# host_board.net
KiCad netlist of a schematic drawn in Altium Designer
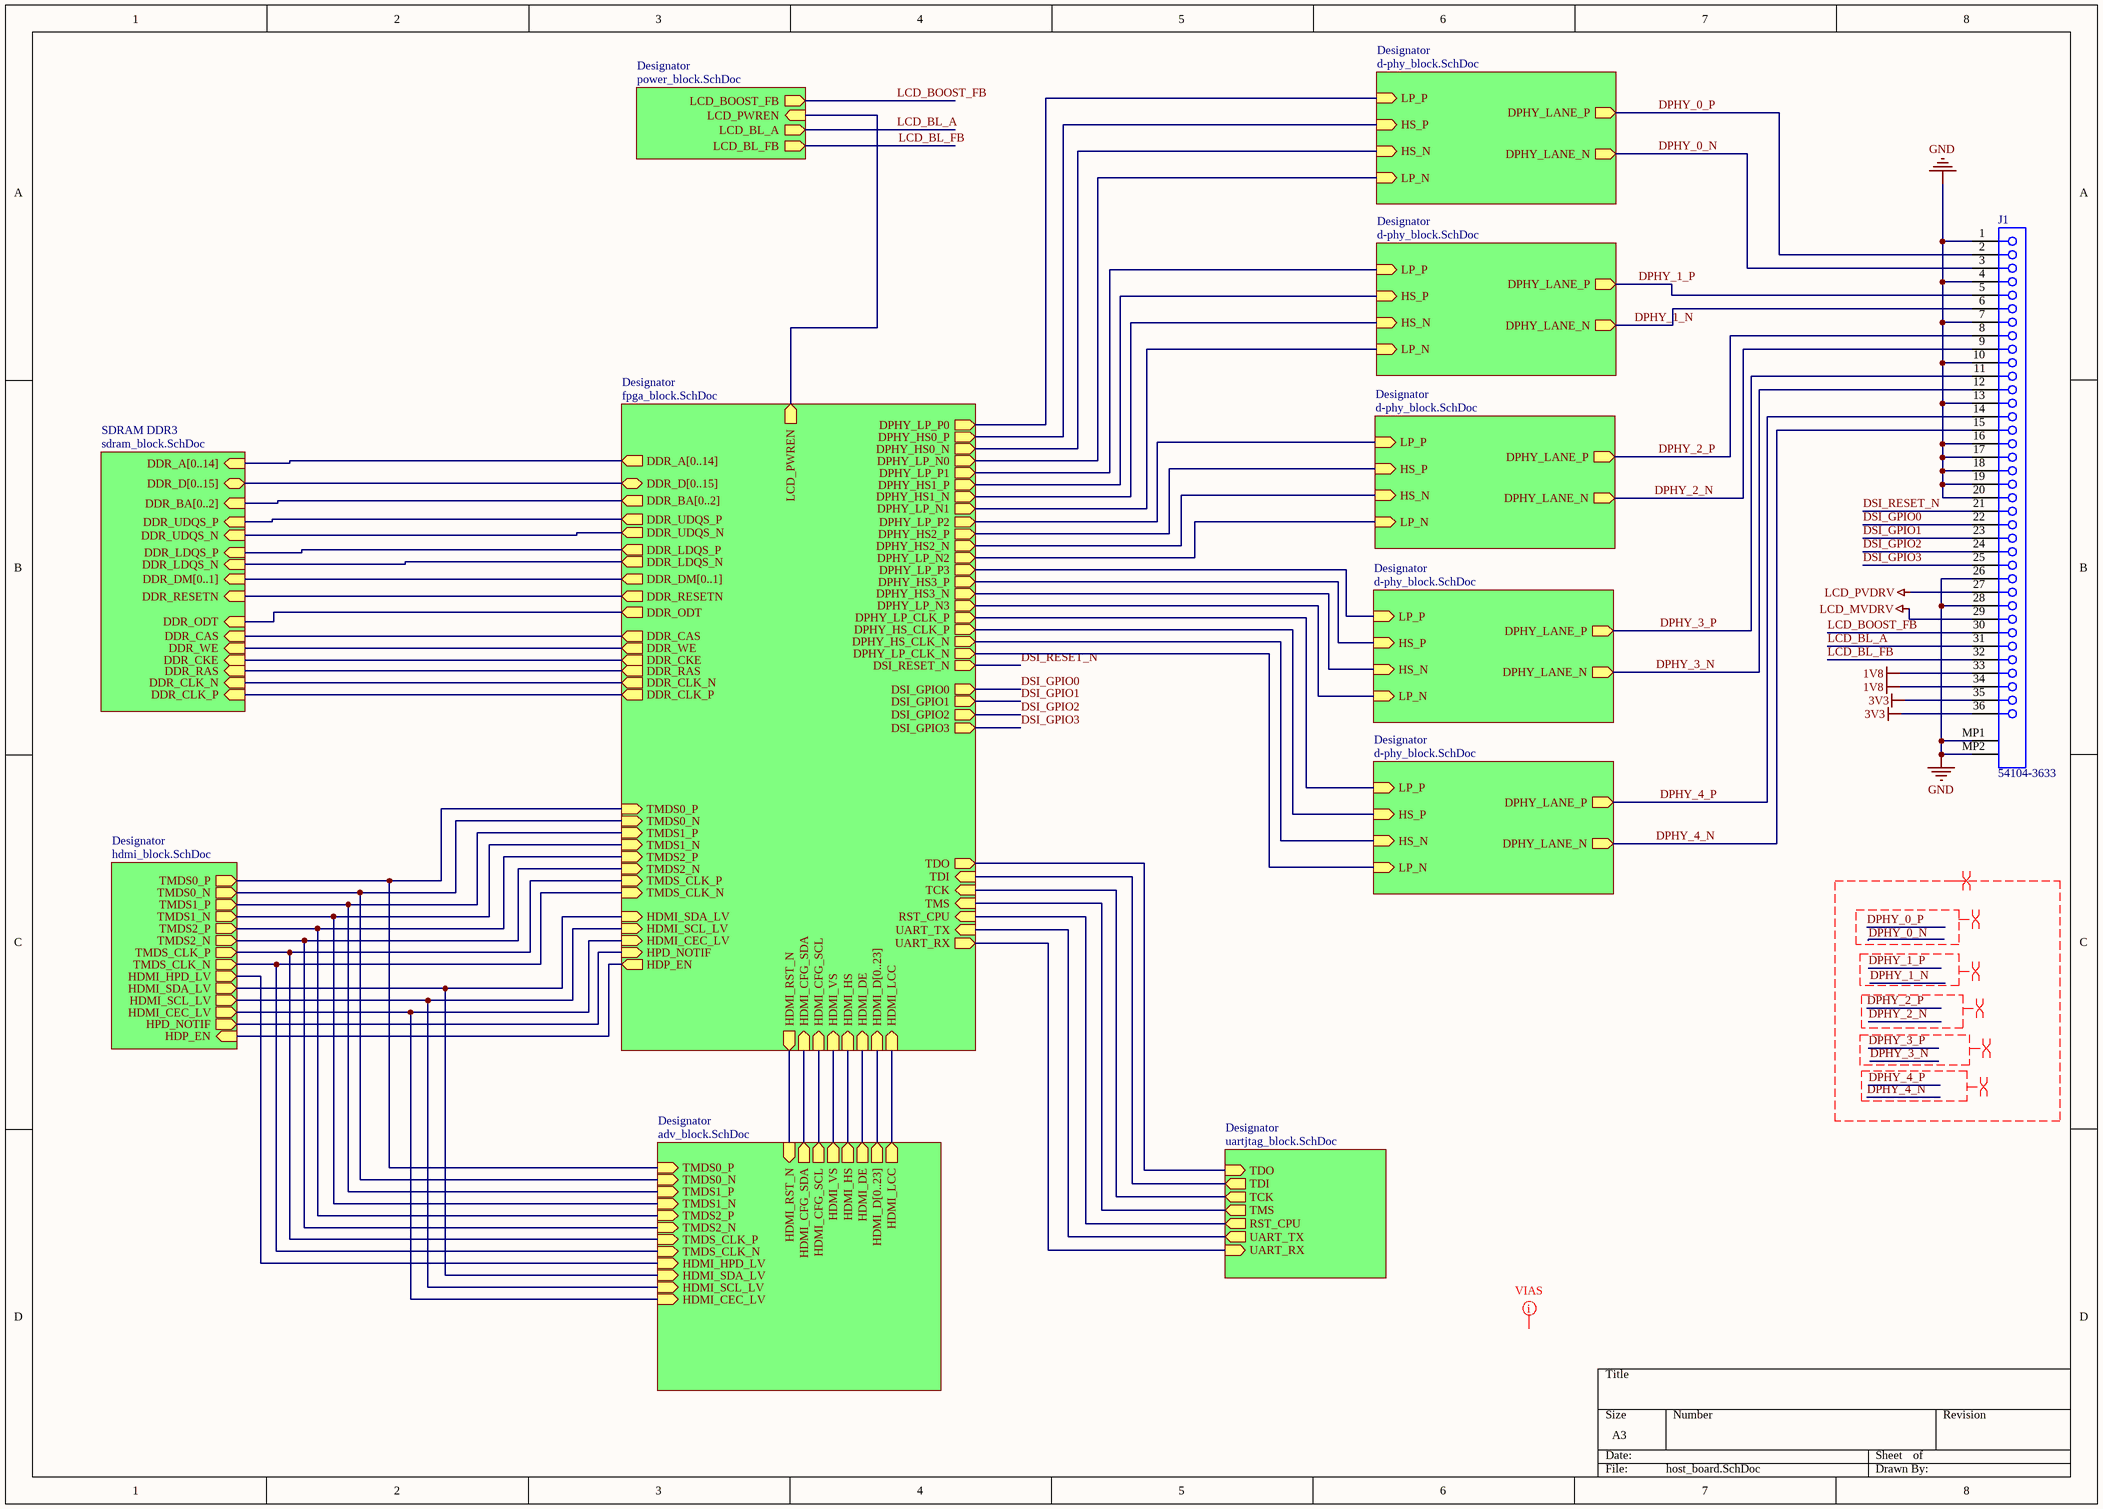
[diagram p0: host_board.SchDoc]

(export (version "E")
  (design (tool "Eeschema 10.0.6"))
  (components
    (comp (ref "J1")
      (value "54104-3633")
      (footprint "MOLX-54104-3633")
      (fields (field (name "MANUFACTURER") "Molex"))
      (libsource (lib "Molex FFC - FPC Connectors (SMT)") (part "54104-3633"))
    )
  )
  (nets
    (net (code "17") (name "/DPHY_0_N") (class "Default")
      (node (ref "J1") (pin "3") (pinfunction "3_3") (pintype "passive"))
    )
    (net (code "18") (name "/DPHY_0_P") (class "Default")
      (node (ref "J1") (pin "2") (pinfunction "2_2") (pintype "passive"))
    )
    (net (code "19") (name "/DPHY_1_N") (class "Default")
      (node (ref "J1") (pin "6") (pinfunction "6_6") (pintype "passive"))
    )
    (net (code "20") (name "/DPHY_1_P") (class "Default")
      (node (ref "J1") (pin "5") (pinfunction "5_5") (pintype "passive"))
    )
    (net (code "21") (name "/DPHY_2_N") (class "Default")
      (node (ref "J1") (pin "9") (pinfunction "9_9") (pintype "passive"))
    )
    (net (code "22") (name "/DPHY_2_P") (class "Default")
      (node (ref "J1") (pin "8") (pinfunction "8_8") (pintype "passive"))
    )
    (net (code "23") (name "/DPHY_3_N") (class "Default")
      (node (ref "J1") (pin "12") (pinfunction "12_12") (pintype "passive"))
    )
    (net (code "24") (name "/DPHY_3_P") (class "Default")
      (node (ref "J1") (pin "11") (pinfunction "11_11") (pintype "passive"))
    )
    (net (code "25") (name "/DPHY_4_N") (class "Default")
      (node (ref "J1") (pin "15") (pinfunction "15_15") (pintype "passive"))
    )
    (net (code "26") (name "/DPHY_4_P") (class "Default")
      (node (ref "J1") (pin "14") (pinfunction "14_14") (pintype "passive"))
    )
    (net (code "53") (name "/DSI_GPIO0") (class "Default")
      (node (ref "J1") (pin "22") (pinfunction "22_22") (pintype "passive"))
    )
    (net (code "54") (name "/DSI_GPIO1") (class "Default")
      (node (ref "J1") (pin "23") (pinfunction "23_23") (pintype "passive"))
    )
    (net (code "55") (name "/DSI_GPIO2") (class "Default")
      (node (ref "J1") (pin "24") (pinfunction "24_24") (pintype "passive"))
    )
    (net (code "56") (name "/DSI_GPIO3") (class "Default")
      (node (ref "J1") (pin "25") (pinfunction "25_25") (pintype "passive"))
    )
    (net (code "57") (name "/DSI_RESET_N") (class "Default")
      (node (ref "J1") (pin "21") (pinfunction "21_21") (pintype "passive"))
    )
    (net (code "72") (name "/LCD_BL_A") (class "Default")
      (node (ref "J1") (pin "31") (pinfunction "31_31") (pintype "passive"))
    )
    (net (code "73") (name "/LCD_BL_FB") (class "Default")
      (node (ref "J1") (pin "32") (pinfunction "32_32") (pintype "passive"))
    )
    (net (code "74") (name "/LCD_BOOST_FB") (class "Default")
      (node (ref "J1") (pin "30") (pinfunction "30_30") (pintype "passive"))
    )
    (net (code "91") (name "1V8") (class "Default")
      (node (ref "J1") (pin "33") (pinfunction "33_33") (pintype "passive"))
      (node (ref "J1") (pin "34") (pinfunction "34_34") (pintype "passive"))
    )
    (net (code "92") (name "3V3") (class "Default")
      (node (ref "J1") (pin "35") (pinfunction "35_35") (pintype "passive"))
      (node (ref "J1") (pin "36") (pinfunction "36_36") (pintype "passive"))
    )
    (net (code "93") (name "GND") (class "Default")
      (node (ref "J1") (pin "1") (pinfunction "1_1") (pintype "passive"))
      (node (ref "J1") (pin "10") (pinfunction "10_10") (pintype "passive"))
      (node (ref "J1") (pin "13") (pinfunction "13_13") (pintype "passive"))
      (node (ref "J1") (pin "16") (pinfunction "16_16") (pintype "passive"))
      (node (ref "J1") (pin "17") (pinfunction "17_17") (pintype "passive"))
      (node (ref "J1") (pin "18") (pinfunction "18_18") (pintype "passive"))
      (node (ref "J1") (pin "19") (pinfunction "19_19") (pintype "passive"))
      (node (ref "J1") (pin "20") (pinfunction "20_20") (pintype "passive"))
      (node (ref "J1") (pin "26") (pinfunction "26_26") (pintype "passive"))
      (node (ref "J1") (pin "28") (pinfunction "28_28") (pintype "passive"))
      (node (ref "J1") (pin "4") (pinfunction "4_4") (pintype "passive"))
      (node (ref "J1") (pin "7") (pinfunction "7_7") (pintype "passive"))
      (node (ref "J1") (pin "MP1") (pinfunction "MP1_MP1") (pintype "passive"))
      (node (ref "J1") (pin "MP2") (pinfunction "MP2_MP2") (pintype "passive"))
    )
    (net (code "94") (name "LCD_MVDRV") (class "Default")
      (node (ref "J1") (pin "29") (pinfunction "29_29") (pintype "passive"))
    )
    (net (code "95") (name "LCD_PVDRV") (class "Default")
      (node (ref "J1") (pin "27") (pinfunction "27_27") (pintype "passive"))
    )
  )
)
